# KIT-ESP32.net
KiCad netlist of a schematic drawn in Altium Designer
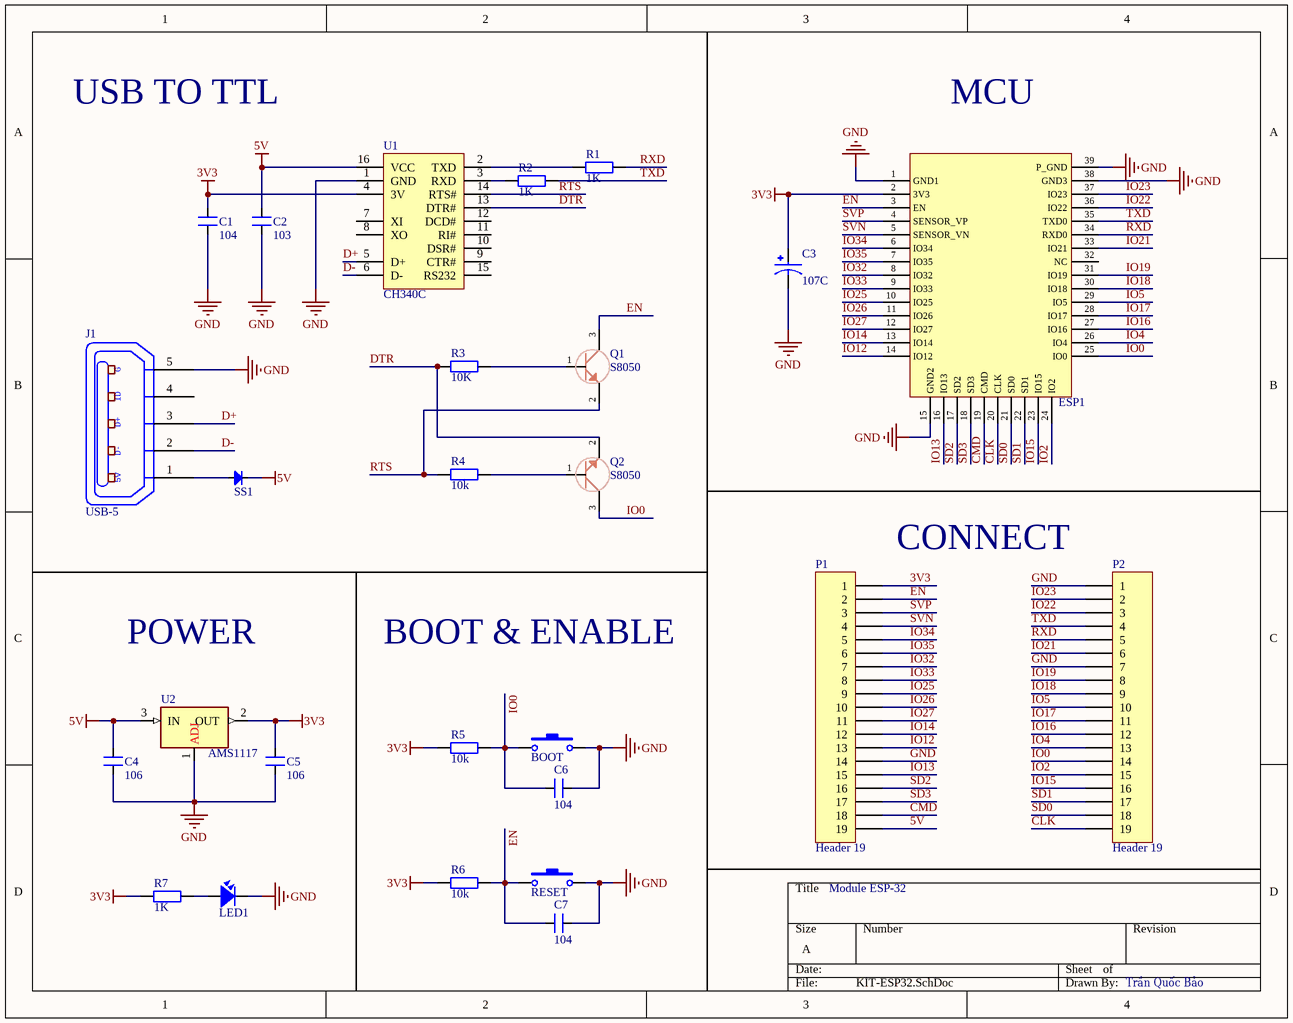
[diagram p0: KIT-ESP32.SchDoc]

(export (version "E")
  (design (tool "Eeschema 10.0.6"))
  (components
    (comp (ref "BOOT")
      (value "SW-SMD")
      (footprint "SW-SMD")
      (description "Switch")
      (fields (field (name "PUBLISHER") "Altium Limited"))
      (libsource (lib "My Library") (part "SW-SMD"))
    )
    (comp (ref "C1")
      (value "104")
      (footprint "SM-0805")
      (description "Cap SMD")
      (libsource (lib "My Library") (part "CM"))
    )
    (comp (ref "C2")
      (value "103")
      (footprint "SM-0805")
      (description "Cap SMD")
      (libsource (lib "My Library") (part "CM"))
    )
    (comp (ref "C3")
      (value "107C")
      (footprint "CAP_TANTALUM_3528")
      (description "Capacitor, Tantalum")
      (fields (field (name "MF") "AVX") (field (name "MP") "TAJB475K025RNJ"))
      (libsource (lib "My Library") (part "CAP_TANTALUM_SMD"))
    )
    (comp (ref "C4")
      (value "106")
      (footprint "SM-0805")
      (description "Cap SMD")
      (libsource (lib "My Library") (part "CM"))
    )
    (comp (ref "C5")
      (value "106")
      (footprint "SM-0805")
      (description "Cap SMD")
      (libsource (lib "My Library") (part "CM"))
    )
    (comp (ref "C6")
      (value "104")
      (footprint "SM-0805")
      (description "Cap SMD")
      (libsource (lib "My Library") (part "CM"))
    )
    (comp (ref "C7")
      (value "104")
      (footprint "SM-0805")
      (description "Cap SMD")
      (libsource (lib "My Library") (part "CM"))
    )
    (comp (ref "ESP1")
      (value "ESP32")
      (footprint "My Library:ESP_WROOM_32")
      (libsource (lib "My Library") (part "ESP-WROOM-32"))
    )
    (comp (ref "J1")
      (value "USB-5")
      (footprint "USB-M1")
      (fields
        (field (name "MANUFACTURER") "FCI")
        (field (name "MANUFACTURER PART NUMBER") "10118193-0001LF")
        (field (name ".CREATOR") "MM")
        (field (name ".CHECKED PCB") "RF")
        (field (name ".CHECKED SCH") "MM")
      )
      (libsource (lib "My Library") (part "USB-5"))
    )
    (comp (ref "LED1") (value "LED") (footprint "LED 3512") (libsource (lib "My Library") (part "LED SMD")))
    (comp (ref "P1")
      (value "Header 19")
      (footprint "HDR1X19")
      (description "Header, 19-Pin")
      (fields (field (name "PUBLISHER") "Altium Limited"))
      (libsource (lib "My Library") (part "Header 19"))
    )
    (comp (ref "P2")
      (value "Header 19")
      (footprint "HDR1X19")
      (description "Header, 19-Pin")
      (fields (field (name "PUBLISHER") "Altium Limited"))
      (libsource (lib "") (part "Header 19_1"))
    )
    (comp (ref "Q1")
      (value "S8050")
      (footprint "SOT23")
      (libsource (lib "My Library") (part "Transitor SMD"))
    )
    (comp (ref "Q2")
      (value "S8050")
      (footprint "SOT23")
      (libsource (lib "My Library") (part "Transitor SMD"))
    )
    (comp (ref "R1")
      (value "1K")
      (footprint "DIEN TRO 0805")
      (description "Resistor SMD 0805")
      (fields (field (name "Comment") "R0805") (field (name "PUBLISHER") "Altium Limited"))
      (libsource (lib "My Library") (part "R0805"))
    )
    (comp (ref "R2")
      (value "1K")
      (footprint "DIEN TRO 0805")
      (description "Resistor SMD 0805")
      (fields (field (name "Comment") "R0805") (field (name "PUBLISHER") "Altium Limited"))
      (libsource (lib "My Library") (part "R0805"))
    )
    (comp (ref "R3")
      (value "10K")
      (footprint "DIEN TRO 0805")
      (description "Resistor SMD 0805")
      (fields (field (name "Comment") "R0805") (field (name "PUBLISHER") "Altium Limited"))
      (libsource (lib "My Library") (part "R0805"))
    )
    (comp (ref "R4")
      (value "10k")
      (footprint "DIEN TRO 0805")
      (description "Resistor SMD 0805")
      (fields (field (name "Comment") "R0805") (field (name "PUBLISHER") "Altium Limited"))
      (libsource (lib "My Library") (part "R0805"))
    )
    (comp (ref "R5")
      (value "10k")
      (footprint "DIEN TRO 0805")
      (description "Resistor SMD 0805")
      (fields (field (name "Comment") "R0805") (field (name "PUBLISHER") "Altium Limited"))
      (libsource (lib "My Library") (part "R0805"))
    )
    (comp (ref "R6")
      (value "10k")
      (footprint "DIEN TRO 0805")
      (description "Resistor SMD 0805")
      (fields (field (name "Comment") "R0805") (field (name "PUBLISHER") "Altium Limited"))
      (libsource (lib "My Library") (part "R0805"))
    )
    (comp (ref "R7")
      (value "1K")
      (footprint "DIEN TRO 0805")
      (description "Resistor SMD 0805")
      (fields (field (name "Comment") "R0805") (field (name "PUBLISHER") "Altium Limited"))
      (libsource (lib "My Library") (part "R0805"))
    )
    (comp (ref "RESET")
      (value "SW-SMD")
      (footprint "SW-SMD")
      (description "Switch")
      (fields (field (name "PUBLISHER") "Altium Limited"))
      (libsource (lib "My Library") (part "SW-SMD"))
    )
    (comp (ref "SS1")
      (value "Diode SMD")
      (footprint "DIO-SMD-106")
      (description "Default Diode")
      (fields (field (name "PUBLISHER") "Altium Limited"))
      (libsource (lib "My Library") (part "Diode SMD"))
    )
    (comp (ref "U1")
      (value "CH340C")
      (footprint "SO16")
      (description "High and Low Side Driver")
      (fields (field (name "PUBLISHER") "Altium Limited"))
      (libsource (lib "My Library") (part "CH340G"))
    )
    (comp (ref "U2")
      (value "AMS1117")
      (footprint "SOT223-4N")
      (description "IC")
      (libsource (lib "My Library") (part "AMS1117"))
    )
  )
  (nets
    (net (code "1") (name "/CLK") (class "Default")
      (node (ref "ESP1") (pin "20") (pinfunction "CLK_20") (pintype "passive"))
      (node (ref "P2") (pin "19") (pinfunction "19_19") (pintype "passive"))
    )
    (net (code "2") (name "/CMD") (class "Default")
      (node (ref "ESP1") (pin "19") (pinfunction "CMD_19") (pintype "passive"))
      (node (ref "P1") (pin "18") (pinfunction "18_18") (pintype "passive"))
    )
    (net (code "3") (name "/D+") (class "Default")
      (node (ref "J1") (pin "3") (pinfunction "P3_3") (pintype "passive"))
      (node (ref "U1") (pin "5") (pinfunction "D+_5") (pintype "passive"))
    )
    (net (code "4") (name "/D-") (class "Default")
      (node (ref "J1") (pin "2") (pinfunction "P2_2") (pintype "passive"))
      (node (ref "U1") (pin "6") (pinfunction "D-_6") (pintype "passive"))
    )
    (net (code "5") (name "/DTR") (class "Default")
      (node (ref "Q2") (pin "2") (pinfunction "E_2") (pintype "passive"))
      (node (ref "R3") (pin "1") (pinfunction "1_1") (pintype "passive"))
      (node (ref "U1") (pin "13") (pinfunction "DTR#_13") (pintype "passive"))
    )
    (net (code "6") (name "/EN") (class "Default")
      (node (ref "C7") (pin "2") (pinfunction "2_2") (pintype "passive"))
      (node (ref "ESP1") (pin "3") (pinfunction "EN_3") (pintype "passive"))
      (node (ref "P1") (pin "2") (pinfunction "2_2") (pintype "passive"))
      (node (ref "Q1") (pin "3") (pinfunction "C_3") (pintype "passive"))
      (node (ref "R6") (pin "2") (pinfunction "2_2") (pintype "passive"))
      (node (ref "RESET") (pin "1") (pinfunction "1_1") (pintype "passive"))
    )
    (net (code "7") (name "/IO0") (class "Default")
      (node (ref "BOOT") (pin "1") (pinfunction "1_1") (pintype "passive"))
      (node (ref "C6") (pin "2") (pinfunction "2_2") (pintype "passive"))
      (node (ref "ESP1") (pin "25") (pinfunction "IO0_25") (pintype "passive"))
      (node (ref "P2") (pin "14") (pinfunction "14_14") (pintype "passive"))
      (node (ref "Q2") (pin "3") (pinfunction "C_3") (pintype "passive"))
      (node (ref "R5") (pin "2") (pinfunction "2_2") (pintype "passive"))
    )
    (net (code "8") (name "/IO2") (class "Default")
      (node (ref "ESP1") (pin "24") (pinfunction "IO2_24") (pintype "passive"))
      (node (ref "P2") (pin "15") (pinfunction "15_15") (pintype "passive"))
    )
    (net (code "9") (name "/IO4") (class "Default")
      (node (ref "ESP1") (pin "26") (pinfunction "IO4_26") (pintype "passive"))
      (node (ref "P2") (pin "13") (pinfunction "13_13") (pintype "passive"))
    )
    (net (code "10") (name "/IO5") (class "Default")
      (node (ref "ESP1") (pin "29") (pinfunction "IO5_29") (pintype "passive"))
      (node (ref "P2") (pin "10") (pinfunction "10_10") (pintype "passive"))
    )
    (net (code "11") (name "/IO12") (class "Default")
      (node (ref "ESP1") (pin "14") (pinfunction "IO12_14") (pintype "passive"))
      (node (ref "P1") (pin "13") (pinfunction "13_13") (pintype "passive"))
    )
    (net (code "12") (name "/IO13") (class "Default")
      (node (ref "ESP1") (pin "16") (pinfunction "IO13_16") (pintype "passive"))
      (node (ref "P1") (pin "15") (pinfunction "15_15") (pintype "passive"))
    )
    (net (code "13") (name "/IO14") (class "Default")
      (node (ref "ESP1") (pin "13") (pinfunction "IO14_13") (pintype "passive"))
      (node (ref "P1") (pin "12") (pinfunction "12_12") (pintype "passive"))
    )
    (net (code "14") (name "/IO15") (class "Default")
      (node (ref "ESP1") (pin "23") (pinfunction "IO15_23") (pintype "passive"))
      (node (ref "P2") (pin "16") (pinfunction "16_16") (pintype "passive"))
    )
    (net (code "15") (name "/IO16") (class "Default")
      (node (ref "ESP1") (pin "27") (pinfunction "IO16_27") (pintype "passive"))
      (node (ref "P2") (pin "12") (pinfunction "12_12") (pintype "passive"))
    )
    (net (code "16") (name "/IO17") (class "Default")
      (node (ref "ESP1") (pin "28") (pinfunction "IO17_28") (pintype "passive"))
      (node (ref "P2") (pin "11") (pinfunction "11_11") (pintype "passive"))
    )
    (net (code "17") (name "/IO18") (class "Default")
      (node (ref "ESP1") (pin "30") (pinfunction "IO18_30") (pintype "passive"))
      (node (ref "P2") (pin "9") (pinfunction "9_9") (pintype "passive"))
    )
    (net (code "18") (name "/IO19") (class "Default")
      (node (ref "ESP1") (pin "31") (pinfunction "IO19_31") (pintype "passive"))
      (node (ref "P2") (pin "8") (pinfunction "8_8") (pintype "passive"))
    )
    (net (code "19") (name "/IO21") (class "Default")
      (node (ref "ESP1") (pin "33") (pinfunction "IO21_33") (pintype "passive"))
      (node (ref "P2") (pin "6") (pinfunction "6_6") (pintype "passive"))
    )
    (net (code "20") (name "/IO22") (class "Default")
      (node (ref "ESP1") (pin "36") (pinfunction "IO22_36") (pintype "passive"))
      (node (ref "P2") (pin "3") (pinfunction "3_3") (pintype "passive"))
    )
    (net (code "21") (name "/IO23") (class "Default")
      (node (ref "ESP1") (pin "37") (pinfunction "IO23_37") (pintype "passive"))
      (node (ref "P2") (pin "2") (pinfunction "2_2") (pintype "passive"))
    )
    (net (code "22") (name "/IO25") (class "Default")
      (node (ref "ESP1") (pin "10") (pinfunction "IO25_10") (pintype "passive"))
      (node (ref "P1") (pin "9") (pinfunction "9_9") (pintype "passive"))
    )
    (net (code "23") (name "/IO26") (class "Default")
      (node (ref "ESP1") (pin "11") (pinfunction "IO26_11") (pintype "passive"))
      (node (ref "P1") (pin "10") (pinfunction "10_10") (pintype "passive"))
    )
    (net (code "24") (name "/IO27") (class "Default")
      (node (ref "ESP1") (pin "12") (pinfunction "IO27_12") (pintype "passive"))
      (node (ref "P1") (pin "11") (pinfunction "11_11") (pintype "passive"))
    )
    (net (code "25") (name "/IO32") (class "Default")
      (node (ref "ESP1") (pin "8") (pinfunction "IO32_8") (pintype "passive"))
      (node (ref "P1") (pin "7") (pinfunction "7_7") (pintype "passive"))
    )
    (net (code "26") (name "/IO33") (class "Default")
      (node (ref "ESP1") (pin "9") (pinfunction "IO33_9") (pintype "passive"))
      (node (ref "P1") (pin "8") (pinfunction "8_8") (pintype "passive"))
    )
    (net (code "27") (name "/IO34") (class "Default")
      (node (ref "ESP1") (pin "6") (pinfunction "IO34_6") (pintype "passive"))
      (node (ref "P1") (pin "5") (pinfunction "5_5") (pintype "passive"))
    )
    (net (code "28") (name "/IO35") (class "Default")
      (node (ref "ESP1") (pin "7") (pinfunction "IO35_7") (pintype "passive"))
      (node (ref "P1") (pin "6") (pinfunction "6_6") (pintype "passive"))
    )
    (net (code "29") (name "/RTS") (class "Default")
      (node (ref "Q1") (pin "2") (pinfunction "E_2") (pintype "passive"))
      (node (ref "R4") (pin "1") (pinfunction "1_1") (pintype "passive"))
      (node (ref "U1") (pin "14") (pinfunction "RTS#_14") (pintype "passive"))
    )
    (net (code "30") (name "/RXD") (class "Default")
      (node (ref "ESP1") (pin "34") (pinfunction "RXD0_34") (pintype "passive"))
      (node (ref "P2") (pin "5") (pinfunction "5_5") (pintype "passive"))
      (node (ref "R1") (pin "2") (pinfunction "2_2") (pintype "passive"))
    )
    (net (code "31") (name "/SD0") (class "Default")
      (node (ref "ESP1") (pin "21") (pinfunction "SD0_21") (pintype "passive"))
      (node (ref "P2") (pin "18") (pinfunction "18_18") (pintype "passive"))
    )
    (net (code "32") (name "/SD1") (class "Default")
      (node (ref "ESP1") (pin "22") (pinfunction "SD1_22") (pintype "passive"))
      (node (ref "P2") (pin "17") (pinfunction "17_17") (pintype "passive"))
    )
    (net (code "33") (name "/SD2") (class "Default")
      (node (ref "ESP1") (pin "17") (pinfunction "SD2_17") (pintype "passive"))
      (node (ref "P1") (pin "16") (pinfunction "16_16") (pintype "passive"))
    )
    (net (code "34") (name "/SD3") (class "Default")
      (node (ref "ESP1") (pin "18") (pinfunction "SD3_18") (pintype "passive"))
      (node (ref "P1") (pin "17") (pinfunction "17_17") (pintype "passive"))
    )
    (net (code "35") (name "/SVN") (class "Default")
      (node (ref "ESP1") (pin "5") (pinfunction "SENSOR_VN_5") (pintype "passive"))
      (node (ref "P1") (pin "4") (pinfunction "4_4") (pintype "passive"))
    )
    (net (code "36") (name "/SVP") (class "Default")
      (node (ref "ESP1") (pin "4") (pinfunction "SENSOR_VP_4") (pintype "passive"))
      (node (ref "P1") (pin "3") (pinfunction "3_3") (pintype "passive"))
    )
    (net (code "37") (name "/TXD") (class "Default")
      (node (ref "ESP1") (pin "35") (pinfunction "TXD0_35") (pintype "passive"))
      (node (ref "P2") (pin "4") (pinfunction "4_4") (pintype "passive"))
      (node (ref "R2") (pin "2") (pinfunction "2_2") (pintype "passive"))
    )
    (net (code "38") (name "3V3") (class "Default")
      (node (ref "C1") (pin "2") (pinfunction "2_2") (pintype "passive"))
      (node (ref "C3") (pin "1") (pinfunction "1_1") (pintype "passive"))
      (node (ref "C5") (pin "2") (pinfunction "2_2") (pintype "passive"))
      (node (ref "ESP1") (pin "2") (pinfunction "3V3_2") (pintype "passive"))
      (node (ref "P1") (pin "1") (pinfunction "1_1") (pintype "passive"))
      (node (ref "R5") (pin "1") (pinfunction "1_1") (pintype "passive"))
      (node (ref "R6") (pin "1") (pinfunction "1_1") (pintype "passive"))
      (node (ref "R7") (pin "1") (pinfunction "1_1") (pintype "passive"))
      (node (ref "U1") (pin "4") (pinfunction "3V_4") (pintype "passive"))
      (node (ref "U2") (pin "2") (pinfunction "OUT_2") (pintype "output"))
    )
    (net (code "39") (name "5V") (class "Default")
      (node (ref "C2") (pin "2") (pinfunction "2_2") (pintype "passive"))
      (node (ref "C4") (pin "2") (pinfunction "2_2") (pintype "passive"))
      (node (ref "P1") (pin "19") (pinfunction "19_19") (pintype "passive"))
      (node (ref "SS1") (pin "2") (pinfunction "K_2") (pintype "passive"))
      (node (ref "U1") (pin "16") (pinfunction "VCC_16") (pintype "passive"))
      (node (ref "U2") (pin "3") (pinfunction "IN_3") (pintype "input"))
    )
    (net (code "40") (name "GND") (class "Default")
      (node (ref "BOOT") (pin "2") (pinfunction "2_2") (pintype "passive"))
      (node (ref "C1") (pin "1") (pinfunction "1_1") (pintype "passive"))
      (node (ref "C2") (pin "1") (pinfunction "1_1") (pintype "passive"))
      (node (ref "C3") (pin "2") (pinfunction "2_2") (pintype "passive"))
      (node (ref "C4") (pin "1") (pinfunction "1_1") (pintype "passive"))
      (node (ref "C5") (pin "1") (pinfunction "1_1") (pintype "passive"))
      (node (ref "C6") (pin "1") (pinfunction "1_1") (pintype "passive"))
      (node (ref "C7") (pin "1") (pinfunction "1_1") (pintype "passive"))
      (node (ref "ESP1") (pin "1") (pinfunction "GND1_1") (pintype "passive"))
      (node (ref "ESP1") (pin "15") (pinfunction "GND2_15") (pintype "passive"))
      (node (ref "ESP1") (pin "38") (pinfunction "GND3_38") (pintype "passive"))
      (node (ref "ESP1") (pin "39") (pinfunction "P_GND_39") (pintype "passive"))
      (node (ref "J1") (pin "5") (pinfunction "P5_5") (pintype "passive"))
      (node (ref "LED1") (pin "2") (pinfunction "2_2") (pintype "passive"))
      (node (ref "P1") (pin "14") (pinfunction "14_14") (pintype "passive"))
      (node (ref "P2") (pin "1") (pinfunction "1_1") (pintype "passive"))
      (node (ref "P2") (pin "7") (pinfunction "7_7") (pintype "passive"))
      (node (ref "RESET") (pin "2") (pinfunction "2_2") (pintype "passive"))
      (node (ref "U1") (pin "1") (pinfunction "GND_1") (pintype "passive"))
      (node (ref "U2") (pin "1") (pinfunction "ADJ_1") (pintype "passive"))
    )
    (net (code "41") (name "Net-(J1-P1)") (class "Default")
      (node (ref "J1") (pin "1") (pinfunction "P1_1") (pintype "passive"))
      (node (ref "SS1") (pin "1") (pinfunction "A_1") (pintype "passive"))
    )
    (net (code "42") (name "Net-(LED1-Pad1)") (class "Default")
      (node (ref "LED1") (pin "1") (pinfunction "1_1") (pintype "passive"))
      (node (ref "R7") (pin "2") (pinfunction "2_2") (pintype "passive"))
    )
    (net (code "43") (name "Net-(Q1-B)") (class "Default")
      (node (ref "Q1") (pin "1") (pinfunction "B_1") (pintype "passive"))
      (node (ref "R3") (pin "2") (pinfunction "2_2") (pintype "passive"))
    )
    (net (code "44") (name "Net-(Q2-B)") (class "Default")
      (node (ref "Q2") (pin "1") (pinfunction "B_1") (pintype "passive"))
      (node (ref "R4") (pin "2") (pinfunction "2_2") (pintype "passive"))
    )
    (net (code "45") (name "Net-(U1-RXD)") (class "Default")
      (node (ref "R2") (pin "1") (pinfunction "1_1") (pintype "passive"))
      (node (ref "U1") (pin "3") (pinfunction "RXD_3") (pintype "passive"))
    )
    (net (code "46") (name "Net-(U1-TXD)") (class "Default")
      (node (ref "R1") (pin "1") (pinfunction "1_1") (pintype "passive"))
      (node (ref "U1") (pin "2") (pinfunction "TXD_2") (pintype "passive"))
    )
    (net (code "47") (name "unconnected-(ESP1-NC-Pad32)") (class "Default")
      (node (ref "ESP1") (pin "32") (pinfunction "NC_32") (pintype "passive"))
    )
    (net (code "48") (name "unconnected-(J1-P4-Pad4)") (class "Default")
      (node (ref "J1") (pin "4") (pinfunction "P4_4") (pintype "passive"))
    )
    (net (code "49") (name "unconnected-(U1-CTR#-Pad9)") (class "Default")
      (node (ref "U1") (pin "9") (pinfunction "CTR#_9") (pintype "passive"))
    )
    (net (code "50") (name "unconnected-(U1-DCD#-Pad12)") (class "Default")
      (node (ref "U1") (pin "12") (pinfunction "DCD#_12") (pintype "passive"))
    )
    (net (code "51") (name "unconnected-(U1-DSR#-Pad10)") (class "Default")
      (node (ref "U1") (pin "10") (pinfunction "DSR#_10") (pintype "passive"))
    )
    (net (code "52") (name "unconnected-(U1-RI#-Pad11)") (class "Default")
      (node (ref "U1") (pin "11") (pinfunction "RI#_11") (pintype "passive"))
    )
    (net (code "53") (name "unconnected-(U1-RS232-Pad15)") (class "Default")
      (node (ref "U1") (pin "15") (pinfunction "RS232_15") (pintype "passive"))
    )
    (net (code "54") (name "unconnected-(U1-XI-Pad7)") (class "Default")
      (node (ref "U1") (pin "7") (pinfunction "XI_7") (pintype "passive"))
    )
    (net (code "55") (name "unconnected-(U1-XO-Pad8)") (class "Default")
      (node (ref "U1") (pin "8") (pinfunction "XO_8") (pintype "passive"))
    )
  )
)
